# Processor.net
KiCad netlist of a schematic drawn in Altium Designer
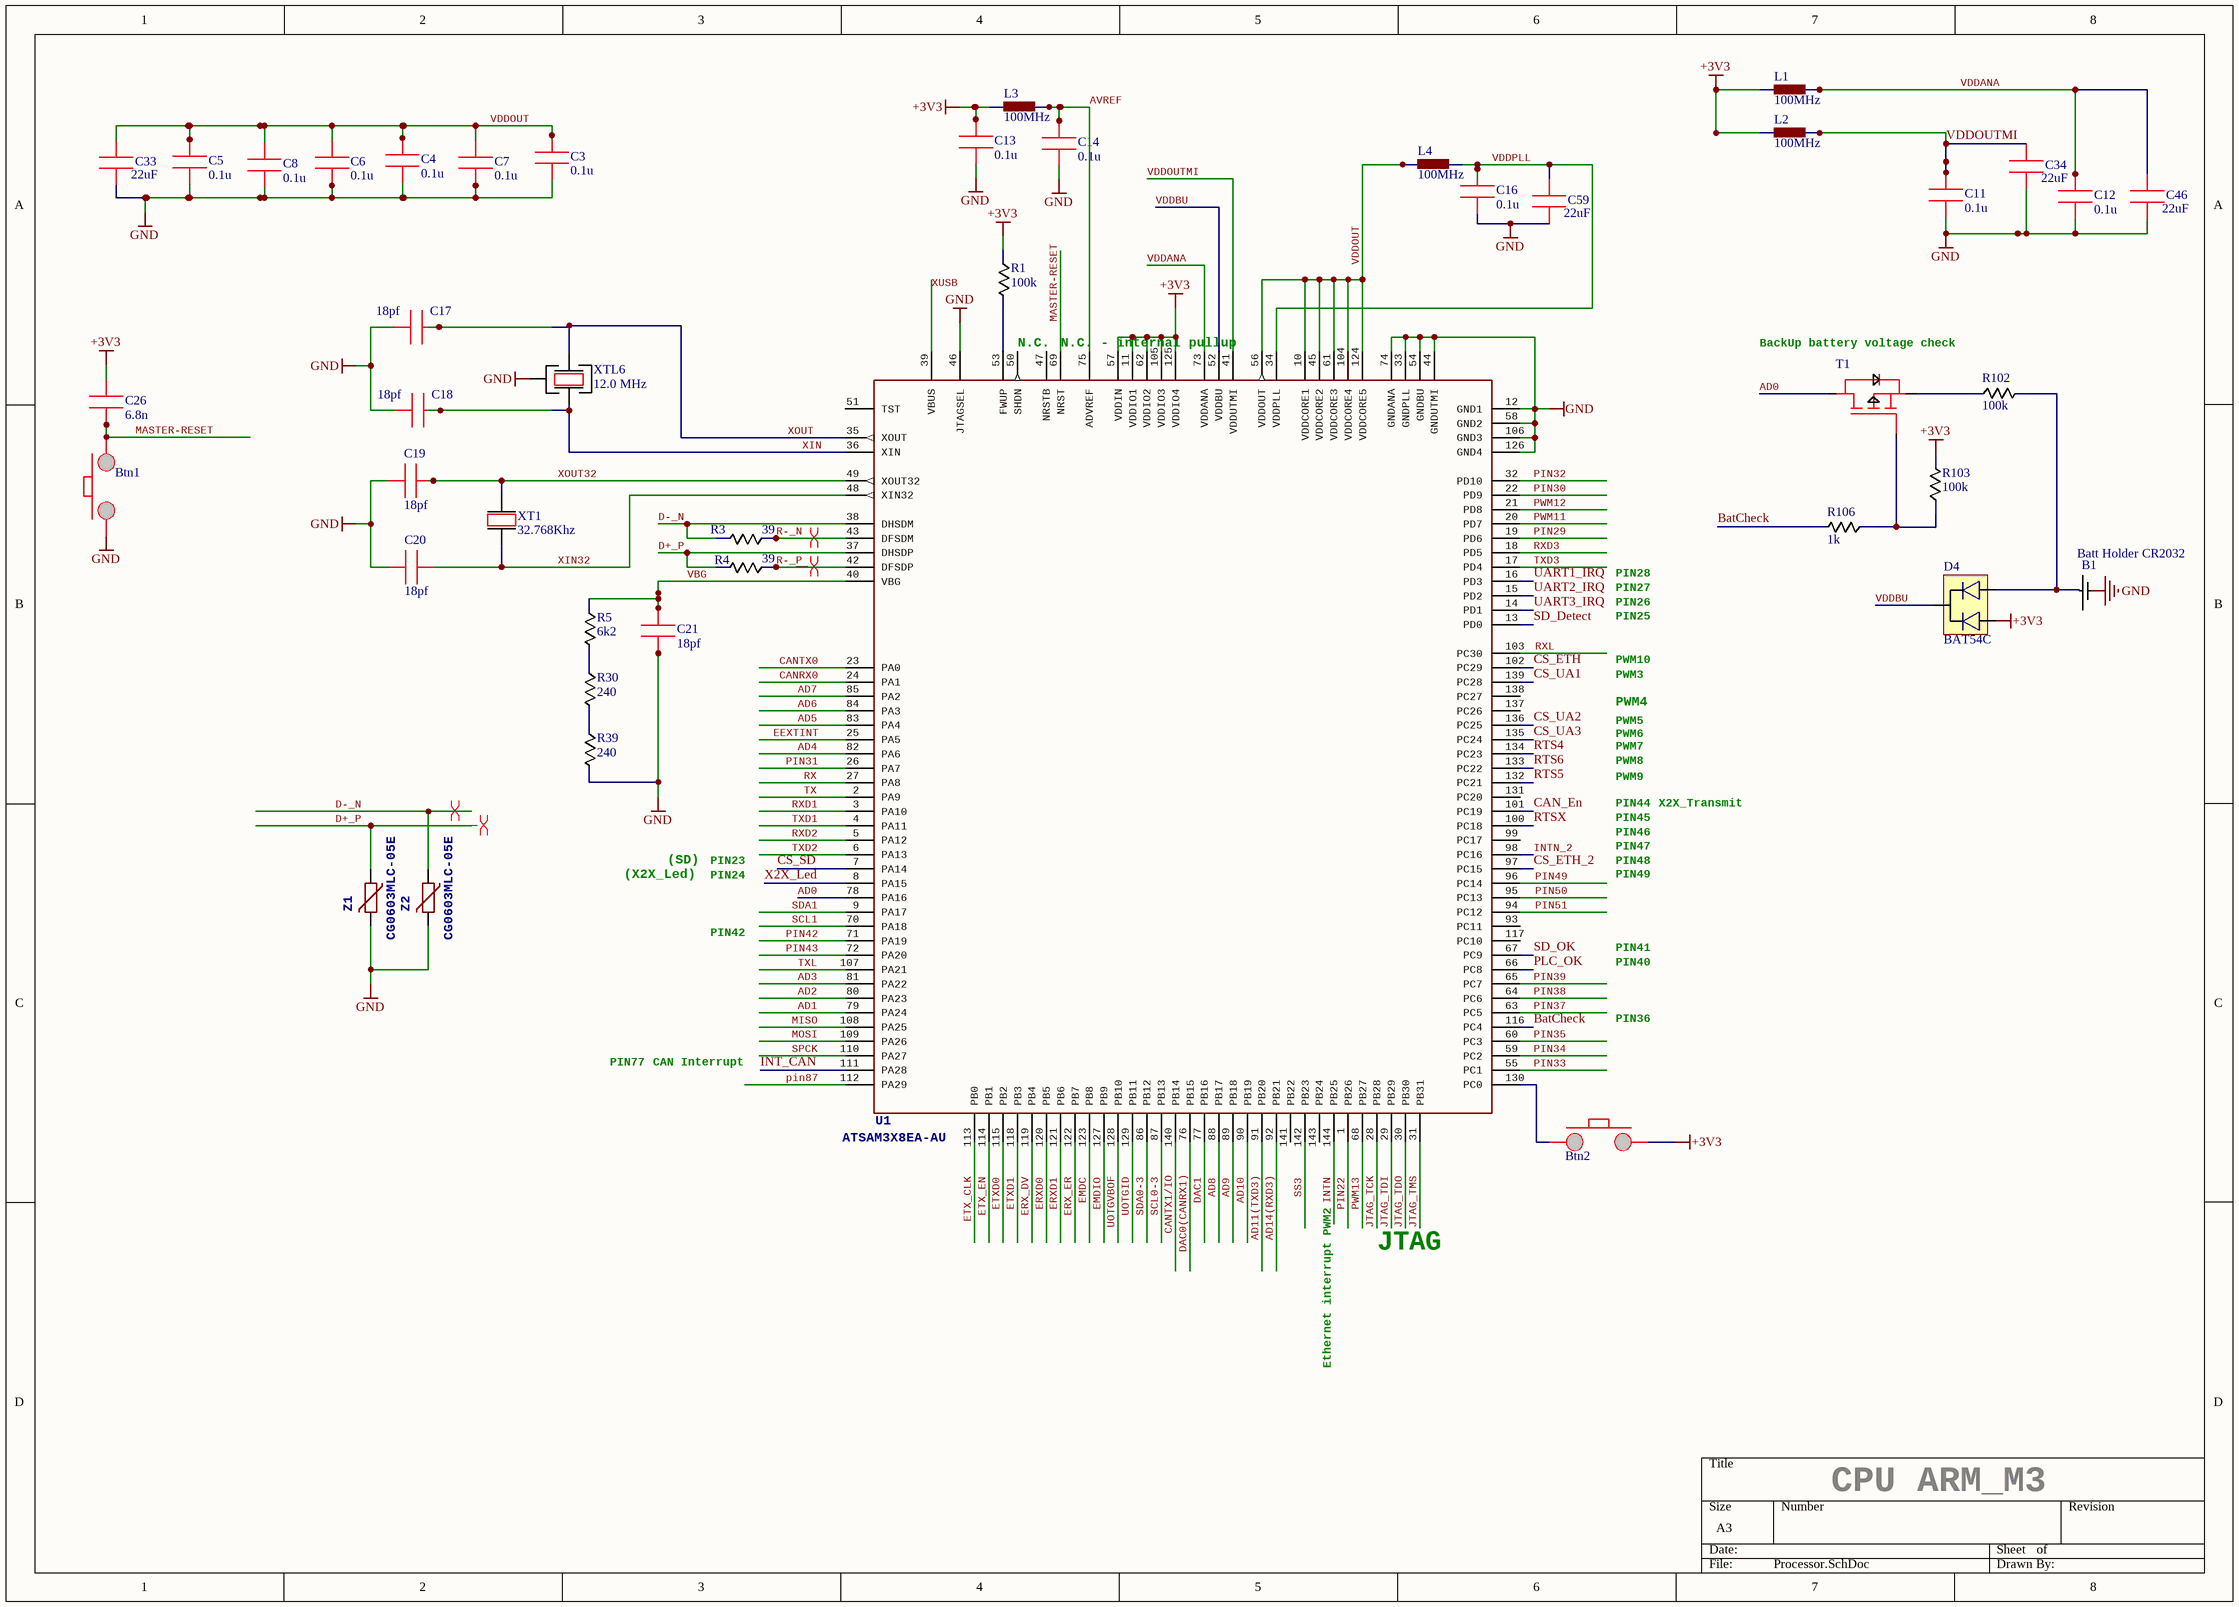
[diagram p0: Processor.SchDoc]

(export (version "E")
  (design (tool "Eeschema 10.0.6"))
  (components
    (comp (ref "B1")
      (value "Batt Holder CR2032")
      (footprint "Batt Holder CR2032")
      (description "1734178-1")
      (libsource (lib "kontr") (part "Batt Holder CR2032"))
    )
    (comp (ref "Btn1")
      (value "Tact Switch")
      (footprint "Tact Switch")
      (description "KLS7-TS6606-4.3-180")
      (libsource (lib "kontr") (part "Tact Switch"))
    )
    (comp (ref "Btn2")
      (value "Tact Switch")
      (footprint "Tact Switch")
      (description "KLS7-TS6606-4.3-180")
      (libsource (lib "kontr") (part "Tact Switch"))
    )
    (comp (ref "C3") (value "0.1u") (footprint "0603 CAP") (libsource (lib "kontr") (part "Capasitor 0805")))
    (comp (ref "C4") (value "0.1u") (footprint "0603 CAP") (libsource (lib "kontr") (part "Capasitor 0805")))
    (comp (ref "C5") (value "0.1u") (footprint "0603 CAP") (libsource (lib "kontr") (part "Capasitor 0805")))
    (comp (ref "C6") (value "0.1u") (footprint "0603 CAP") (libsource (lib "kontr") (part "Capasitor 0805")))
    (comp (ref "C7") (value "0.1u") (footprint "0603 CAP") (libsource (lib "kontr") (part "Capasitor 0805")))
    (comp (ref "C8") (value "0.1u") (footprint "0603 CAP") (libsource (lib "kontr") (part "Capasitor 0805")))
    (comp (ref "C11") (value "0.1u") (footprint "0603 CAP") (libsource (lib "kontr") (part "Capasitor 0805")))
    (comp (ref "C12") (value "0.1u") (footprint "0603 CAP") (libsource (lib "kontr") (part "Capasitor 0805")))
    (comp (ref "C13") (value "0.1u") (footprint "0603 CAP") (libsource (lib "kontr") (part "Capasitor 0805")))
    (comp (ref "C14") (value "0.1u") (footprint "0603 CAP") (libsource (lib "kontr") (part "Capasitor 0805")))
    (comp (ref "C16") (value "0.1u") (footprint "0603 CAP") (libsource (lib "kontr") (part "Capasitor 0805")))
    (comp (ref "C17")
      (value "18pf")
      (footprint "0603 CAP")
      (description "GRM1885C1H180JA01D")
      (libsource (lib "kontr") (part "Capasitor 0805"))
    )
    (comp (ref "C18")
      (value "18pf")
      (footprint "0603 CAP")
      (description "GRM1885C1H180JA01D")
      (libsource (lib "kontr") (part "Capasitor 0805"))
    )
    (comp (ref "C19")
      (value "18pf")
      (footprint "0603 CAP")
      (description "GRM1885C1H180JA01D")
      (libsource (lib "kontr") (part "Capasitor 0805"))
    )
    (comp (ref "C20")
      (value "18pf")
      (footprint "0603 CAP")
      (description "GRM1885C1H180JA01D")
      (libsource (lib "kontr") (part "Capasitor 0805"))
    )
    (comp (ref "C21")
      (value "18pf")
      (footprint "0603 CAP")
      (description "GRM1885C1H180JA01D")
      (libsource (lib "kontr") (part "Capasitor 0805"))
    )
    (comp (ref "C26")
      (value "6.8n")
      (footprint "0603 CAP")
      (description "CC0603KRX7R9BB682")
      (libsource (lib "kontr") (part "0603 CAP"))
    )
    (comp (ref "C33")
      (value "22uF")
      (footprint "CAP CER 1210 NP")
      (description "CC1210KKX5R7BB226")
      (libsource (lib "kontr") (part "0805 Cap"))
    )
    (comp (ref "C34")
      (value "22uF")
      (footprint "CAP CER 1210 NP")
      (description "CC1210KKX5R7BB226")
      (libsource (lib "kontr") (part "0805 Cap"))
    )
    (comp (ref "C46")
      (value "22uF")
      (footprint "CAP CER 1210 NP")
      (description "CC1210KKX5R7BB226")
      (libsource (lib "kontr") (part "0805 Cap"))
    )
    (comp (ref "C59")
      (value "22uF")
      (footprint "CAP CER 1210 NP")
      (description "CC1210KKX5R7BB226")
      (libsource (lib "kontr") (part "0805 Cap"))
    )
    (comp (ref "D4") (value "BAT54C") (footprint "SOT23") (libsource (lib "kontr") (part "BAT54C")))
    (comp (ref "L1")
      (value "100MHz")
      (footprint "0805")
      (description "BLM21PG220SN1D")
      (libsource (lib "kontr") (part "BLM21PG220SN1D"))
    )
    (comp (ref "L2")
      (value "100MHz")
      (footprint "0805")
      (description "BLM21PG220SN1D")
      (libsource (lib "kontr") (part "BLM21PG220SN1D"))
    )
    (comp (ref "L3")
      (value "100MHz")
      (footprint "0805")
      (description "BLM21PG220SN1D")
      (libsource (lib "kontr") (part "BLM21PG220SN1D"))
    )
    (comp (ref "L4")
      (value "100MHz")
      (footprint "0805")
      (description "BLM21PG220SN1D")
      (libsource (lib "kontr") (part "BLM21PG220SN1D"))
    )
    (comp (ref "R1")
      (value "100k")
      (footprint "0603 - RES")
      (description "RC0603FR-07100KL")
      (libsource (lib "kontr") (part "Resistor 0805"))
    )
    (comp (ref "R3")
      (value "39")
      (footprint "0603 - RES")
      (description "0805 SMD Resistor")
      (libsource (lib "kontr") (part "Resistor 0805"))
    )
    (comp (ref "R4")
      (value "39")
      (footprint "0603 - RES")
      (description "0805 SMD Resistor")
      (libsource (lib "kontr") (part "Resistor 0805"))
    )
    (comp (ref "R5")
      (value "6k2")
      (footprint "0603 - RES")
      (description "0805 SMD Resistor")
      (libsource (lib "kontr") (part "Resistor 0805"))
    )
    (comp (ref "R30")
      (value "240")
      (footprint "0603 - RES")
      (description "0805 SMD Resistor")
      (libsource (lib "kontr") (part "Resistor 0805"))
    )
    (comp (ref "R39")
      (value "240")
      (footprint "0603 - RES")
      (description "0805 SMD Resistor")
      (libsource (lib "kontr") (part "Resistor 0805"))
    )
    (comp (ref "R102")
      (value "100k")
      (footprint "0603 - RES")
      (description "RC0603FR-07100KL")
      (libsource (lib "kontr") (part "Resistor 0805"))
    )
    (comp (ref "R103")
      (value "100k")
      (footprint "0603 - RES")
      (description "RC0603FR-07100KL")
      (libsource (lib "kontr") (part "Resistor 0805"))
    )
    (comp (ref "R106")
      (value "1k")
      (footprint "0603 - RES")
      (description "RC0603FR-078K2")
      (libsource (lib "kontr") (part "Resistor 0805"))
    )
    (comp (ref "T1") (value "IRLML6302") (footprint "SOT23") (libsource (lib "kontr") (part "IRLML6302")))
    (comp (ref "U1")
      (value "ATSAM3X8EA-AU")
      (footprint "LQFP144")
      (libsource (lib "SmartPrj") (part "ATSAM3X/AAU"))
    )
    (comp (ref "XT1")
      (value "32.768Khz")
      (footprint "XTAL KX-327T")
      (description "KX – 327XS")
      (libsource (lib "kontr") (part "KX – 327XS"))
    )
    (comp (ref "XTL6")
      (value "12.0 MHz")
      (footprint "XTAL KX-7T")
      (description "Geyer KX-7 12.0 MHz")
      (libsource (lib "PLC M3") (part "KX-7"))
    )
    (comp (ref "Z1")
      (value "CG0603MLC-05E")
      (footprint "0603 - RES")
      (description "<b>VARISTOR</b>")
      (libsource (lib "varistor") (part "VARISTORCN0603"))
    )
    (comp (ref "Z2")
      (value "CG0603MLC-05E")
      (footprint "0603 - RES")
      (description "<b>VARISTOR</b>")
      (libsource (lib "varistor") (part "VARISTORCN0603"))
    )
  )
  (nets
    (net (code "1") (name "+3V3") (class "Default")
      (node (ref "Btn2") (pin "1") (pinfunction "1_1") (pintype "passive"))
      (node (ref "C13") (pin "2") (pinfunction "2_2") (pintype "passive"))
      (node (ref "C26") (pin "2") (pinfunction "2_2") (pintype "passive"))
      (node (ref "D4") (pin "1") (pinfunction "1_1") (pintype "passive"))
      (node (ref "L1") (pin "1") (pintype "passive"))
      (node (ref "L2") (pin "1") (pintype "passive"))
      (node (ref "L3") (pin "1") (pintype "passive"))
      (node (ref "R1") (pin "1") (pintype "passive"))
      (node (ref "R103") (pin "2") (pintype "passive"))
      (node (ref "U1") (pin "105") (pinfunction "VDDIO3_105") (pintype "power_in"))
      (node (ref "U1") (pin "11") (pinfunction "VDDIO1_11") (pintype "power_in"))
      (node (ref "U1") (pin "125") (pinfunction "VDDIO4_125") (pintype "power_in"))
      (node (ref "U1") (pin "57") (pinfunction "VDDIN_57") (pintype "power_in"))
      (node (ref "U1") (pin "62") (pinfunction "VDDIO2_62") (pintype "power_in"))
    )
    (net (code "2") (name "/AD0") (class "Default")
      (node (ref "T1") (pin "3") (pinfunction "3_3") (pintype "passive"))
      (node (ref "U1") (pin "78") (pinfunction "PA16_78") (pintype "passive"))
    )
    (net (code "3") (name "/AD1") (class "Default")
      (node (ref "U1") (pin "79") (pinfunction "PA24_79") (pintype "passive"))
    )
    (net (code "4") (name "/AD2") (class "Default")
      (node (ref "U1") (pin "80") (pinfunction "PA23_80") (pintype "passive"))
    )
    (net (code "5") (name "/AD3") (class "Default")
      (node (ref "U1") (pin "81") (pinfunction "PA22_81") (pintype "passive"))
    )
    (net (code "6") (name "/AD4") (class "Default")
      (node (ref "U1") (pin "82") (pinfunction "PA6_82") (pintype "passive"))
    )
    (net (code "7") (name "/AD5") (class "Default")
      (node (ref "U1") (pin "83") (pinfunction "PA4_83") (pintype "passive"))
    )
    (net (code "8") (name "/AD6") (class "Default")
      (node (ref "U1") (pin "84") (pinfunction "PA3_84") (pintype "passive"))
    )
    (net (code "9") (name "/AD7") (class "Default")
      (node (ref "U1") (pin "85") (pinfunction "PA2_85") (pintype "passive"))
    )
    (net (code "10") (name "/AD8") (class "Default")
      (node (ref "U1") (pin "88") (pinfunction "PB17_88") (pintype "passive"))
    )
    (net (code "11") (name "/AD9") (class "Default")
      (node (ref "U1") (pin "89") (pinfunction "PB18_89") (pintype "passive"))
    )
    (net (code "12") (name "/AD10") (class "Default")
      (node (ref "U1") (pin "90") (pinfunction "PB19_90") (pintype "passive"))
    )
    (net (code "13") (name "/AD11(TXD3)") (class "Default")
      (node (ref "U1") (pin "91") (pinfunction "PB20_91") (pintype "passive"))
    )
    (net (code "14") (name "/AD14(RXD3)") (class "Default")
      (node (ref "U1") (pin "92") (pinfunction "PB21_92") (pintype "passive"))
    )
    (net (code "15") (name "/AVREF") (class "Default")
      (node (ref "C14") (pin "2") (pinfunction "2_2") (pintype "passive"))
      (node (ref "L3") (pin "2") (pintype "passive"))
      (node (ref "U1") (pin "75") (pinfunction "ADVREF_75") (pintype "power_in"))
    )
    (net (code "16") (name "/BatCheck") (class "Default")
      (node (ref "R106") (pin "2") (pintype "passive"))
      (node (ref "U1") (pin "116") (pinfunction "PC4_116") (pintype "passive"))
    )
    (net (code "17") (name "/CANRX0") (class "Default")
      (node (ref "U1") (pin "24") (pinfunction "PA1_24") (pintype "passive"))
    )
    (net (code "18") (name "/CANTX0") (class "Default")
      (node (ref "U1") (pin "23") (pinfunction "PA0_23") (pintype "passive"))
    )
    (net (code "19") (name "/CANTX1{slash}IO") (class "Default")
      (node (ref "U1") (pin "140") (pinfunction "PB14_140") (pintype "passive"))
    )
    (net (code "20") (name "/CAN_En") (class "Default")
      (node (ref "U1") (pin "101") (pinfunction "PC19_101") (pintype "passive"))
    )
    (net (code "21") (name "/CS_ETH") (class "Default")
      (node (ref "U1") (pin "102") (pinfunction "PC29_102") (pintype "passive"))
    )
    (net (code "22") (name "/CS_ETH_2") (class "Default")
      (node (ref "U1") (pin "97") (pinfunction "PC15_97") (pintype "passive"))
    )
    (net (code "23") (name "/CS_SD") (class "Default")
      (node (ref "U1") (pin "7") (pinfunction "PA14_7") (pintype "passive"))
    )
    (net (code "24") (name "/CS_UA1") (class "Default")
      (node (ref "U1") (pin "139") (pinfunction "PC28_139") (pintype "passive"))
    )
    (net (code "25") (name "/CS_UA2") (class "Default")
      (node (ref "U1") (pin "136") (pinfunction "PC25_136") (pintype "passive"))
    )
    (net (code "26") (name "/CS_UA3") (class "Default")
      (node (ref "U1") (pin "135") (pinfunction "PC24_135") (pintype "passive"))
    )
    (net (code "27") (name "/D+_P") (class "Default")
      (node (ref "R4") (pin "2") (pintype "passive"))
      (node (ref "U1") (pin "37") (pinfunction "DHSDP_37") (pintype "passive"))
      (node (ref "Z1") (pin "1") (pinfunction "1_1") (pintype "passive"))
    )
    (net (code "28") (name "/D-_N") (class "Default")
      (node (ref "R3") (pin "2") (pintype "passive"))
      (node (ref "U1") (pin "38") (pinfunction "DHSDM_38") (pintype "passive"))
      (node (ref "Z2") (pin "1") (pinfunction "1_1") (pintype "passive"))
    )
    (net (code "29") (name "/DAC0(CANRX1)") (class "Default")
      (node (ref "U1") (pin "76") (pinfunction "PB15_76") (pintype "passive"))
    )
    (net (code "30") (name "/DAC1") (class "Default")
      (node (ref "U1") (pin "77") (pinfunction "PB16_77") (pintype "passive"))
    )
    (net (code "31") (name "/EEXTINT") (class "Default")
      (node (ref "U1") (pin "25") (pinfunction "PA5_25") (pintype "passive"))
    )
    (net (code "32") (name "/EMDC") (class "Default")
      (node (ref "U1") (pin "123") (pinfunction "PB8_123") (pintype "passive"))
    )
    (net (code "33") (name "/EMDIO") (class "Default")
      (node (ref "U1") (pin "127") (pinfunction "PB9_127") (pintype "passive"))
    )
    (net (code "34") (name "/ERXD0") (class "Default")
      (node (ref "U1") (pin "120") (pinfunction "PB5_120") (pintype "passive"))
    )
    (net (code "35") (name "/ERXD1") (class "Default")
      (node (ref "U1") (pin "121") (pinfunction "PB6_121") (pintype "passive"))
    )
    (net (code "36") (name "/ERX_DV") (class "Default")
      (node (ref "U1") (pin "119") (pinfunction "PB4_119") (pintype "passive"))
    )
    (net (code "37") (name "/ERX_ER") (class "Default")
      (node (ref "U1") (pin "122") (pinfunction "PB7_122") (pintype "passive"))
    )
    (net (code "38") (name "/ETXD0") (class "Default")
      (node (ref "U1") (pin "115") (pinfunction "PB2_115") (pintype "passive"))
    )
    (net (code "39") (name "/ETXD1") (class "Default")
      (node (ref "U1") (pin "118") (pinfunction "PB3_118") (pintype "passive"))
    )
    (net (code "40") (name "/ETX_CLK") (class "Default")
      (node (ref "U1") (pin "113") (pinfunction "PB0_113") (pintype "passive"))
    )
    (net (code "41") (name "/ETX_EN") (class "Default")
      (node (ref "U1") (pin "114") (pinfunction "PB1_114") (pintype "passive"))
    )
    (net (code "42") (name "/INTN") (class "Default")
      (node (ref "U1") (pin "144") (pinfunction "PB25_144") (pintype "passive"))
    )
    (net (code "43") (name "/INTN_2") (class "Default")
      (node (ref "U1") (pin "98") (pinfunction "PC16_98") (pintype "passive"))
    )
    (net (code "44") (name "/INT_CAN") (class "Default")
      (node (ref "U1") (pin "111") (pinfunction "PA28_111") (pintype "passive"))
    )
    (net (code "45") (name "/JTAG_TCK") (class "Default")
      (node (ref "U1") (pin "28") (pinfunction "PB28_28") (pintype "passive"))
    )
    (net (code "46") (name "/JTAG_TDI") (class "Default")
      (node (ref "U1") (pin "29") (pinfunction "PB29_29") (pintype "passive"))
    )
    (net (code "47") (name "/JTAG_TDO") (class "Default")
      (node (ref "U1") (pin "30") (pinfunction "PB30_30") (pintype "passive"))
    )
    (net (code "48") (name "/JTAG_TMS") (class "Default")
      (node (ref "U1") (pin "31") (pinfunction "PB31_31") (pintype "passive"))
    )
    (net (code "49") (name "/MASTER-RESET") (class "Default")
      (node (ref "Btn1") (pin "1") (pinfunction "1_1") (pintype "passive"))
      (node (ref "C26") (pin "1") (pinfunction "1_1") (pintype "passive"))
      (node (ref "U1") (pin "69") (pinfunction "NRST_69") (pintype "passive"))
    )
    (net (code "50") (name "/MISO") (class "Default")
      (node (ref "U1") (pin "108") (pinfunction "PA25_108") (pintype "passive"))
    )
    (net (code "51") (name "/MOSI") (class "Default")
      (node (ref "U1") (pin "109") (pinfunction "PA26_109") (pintype "passive"))
    )
    (net (code "52") (name "/PIN22") (class "Default")
      (node (ref "U1") (pin "1") (pinfunction "PB26_1") (pintype "passive"))
    )
    (net (code "53") (name "/PIN29") (class "Default")
      (node (ref "U1") (pin "19") (pinfunction "PD6_19") (pintype "passive"))
    )
    (net (code "54") (name "/PIN30") (class "Default")
      (node (ref "U1") (pin "22") (pinfunction "PD9_22") (pintype "passive"))
    )
    (net (code "55") (name "/PIN31") (class "Default")
      (node (ref "U1") (pin "26") (pinfunction "PA7_26") (pintype "passive"))
    )
    (net (code "56") (name "/PIN32") (class "Default")
      (node (ref "U1") (pin "32") (pinfunction "PD10_32") (pintype "passive"))
    )
    (net (code "57") (name "/PIN33") (class "Default")
      (node (ref "U1") (pin "55") (pinfunction "PC1_55") (pintype "passive"))
    )
    (net (code "58") (name "/PIN34") (class "Default")
      (node (ref "U1") (pin "59") (pinfunction "PC2_59") (pintype "passive"))
    )
    (net (code "59") (name "/PIN35") (class "Default")
      (node (ref "U1") (pin "60") (pinfunction "PC3_60") (pintype "passive"))
    )
    (net (code "60") (name "/PIN37") (class "Default")
      (node (ref "U1") (pin "63") (pinfunction "PC5_63") (pintype "passive"))
    )
    (net (code "61") (name "/PIN38") (class "Default")
      (node (ref "U1") (pin "64") (pinfunction "PC6_64") (pintype "passive"))
    )
    (net (code "62") (name "/PIN39") (class "Default")
      (node (ref "U1") (pin "65") (pinfunction "PC7_65") (pintype "passive"))
    )
    (net (code "63") (name "/PIN42") (class "Default")
      (node (ref "U1") (pin "71") (pinfunction "PA19_71") (pintype "passive"))
    )
    (net (code "64") (name "/PIN43") (class "Default")
      (node (ref "U1") (pin "72") (pinfunction "PA20_72") (pintype "passive"))
    )
    (net (code "65") (name "/PIN49") (class "Default")
      (node (ref "U1") (pin "96") (pinfunction "PC14_96") (pintype "passive"))
    )
    (net (code "66") (name "/PIN50") (class "Default")
      (node (ref "U1") (pin "95") (pinfunction "PC13_95") (pintype "passive"))
    )
    (net (code "67") (name "/PIN51") (class "Default")
      (node (ref "U1") (pin "94") (pinfunction "PC12_94") (pintype "passive"))
    )
    (net (code "68") (name "/PLC_OK") (class "Default")
      (node (ref "U1") (pin "66") (pinfunction "PC8_66") (pintype "passive"))
    )
    (net (code "69") (name "/PWM11") (class "Default")
      (node (ref "U1") (pin "20") (pinfunction "PD7_20") (pintype "passive"))
    )
    (net (code "70") (name "/PWM12") (class "Default")
      (node (ref "U1") (pin "21") (pinfunction "PD8_21") (pintype "passive"))
    )
    (net (code "71") (name "/PWM13") (class "Default")
      (node (ref "U1") (pin "68") (pinfunction "PB27_68") (pintype "passive"))
    )
    (net (code "72") (name "/R-_N") (class "Default")
      (node (ref "R3") (pin "1") (pintype "passive"))
      (node (ref "U1") (pin "43") (pinfunction "DFSDM_43") (pintype "passive"))
    )
    (net (code "73") (name "/R-_P") (class "Default")
      (node (ref "R4") (pin "1") (pintype "passive"))
      (node (ref "U1") (pin "42") (pinfunction "DFSDP_42") (pintype "passive"))
    )
    (net (code "74") (name "/RTS4") (class "Default")
      (node (ref "U1") (pin "134") (pinfunction "PC23_134") (pintype "passive"))
    )
    (net (code "75") (name "/RTS5") (class "Default")
      (node (ref "U1") (pin "132") (pinfunction "PC21_132") (pintype "passive"))
    )
    (net (code "76") (name "/RTS6") (class "Default")
      (node (ref "U1") (pin "133") (pinfunction "PC22_133") (pintype "passive"))
    )
    (net (code "77") (name "/RTSX") (class "Default")
      (node (ref "U1") (pin "100") (pinfunction "PC18_100") (pintype "passive"))
    )
    (net (code "78") (name "/RX") (class "Default")
      (node (ref "U1") (pin "27") (pinfunction "PA8_27") (pintype "passive"))
    )
    (net (code "79") (name "/RXD1") (class "Default")
      (node (ref "U1") (pin "3") (pinfunction "PA10_3") (pintype "passive"))
    )
    (net (code "80") (name "/RXD2") (class "Default")
      (node (ref "U1") (pin "5") (pinfunction "PA12_5") (pintype "passive"))
    )
    (net (code "81") (name "/RXD3") (class "Default")
      (node (ref "U1") (pin "18") (pinfunction "PD5_18") (pintype "passive"))
    )
    (net (code "82") (name "/RXL") (class "Default")
      (node (ref "U1") (pin "103") (pinfunction "PC30_103") (pintype "passive"))
    )
    (net (code "83") (name "/SCL0-3") (class "Default")
      (node (ref "U1") (pin "87") (pinfunction "PB13_87") (pintype "passive"))
    )
    (net (code "84") (name "/SCL1") (class "Default")
      (node (ref "U1") (pin "70") (pinfunction "PA18_70") (pintype "passive"))
    )
    (net (code "85") (name "/SDA0-3") (class "Default")
      (node (ref "U1") (pin "86") (pinfunction "PB12_86") (pintype "passive"))
    )
    (net (code "86") (name "/SDA1") (class "Default")
      (node (ref "U1") (pin "9") (pinfunction "PA17_9") (pintype "passive"))
    )
    (net (code "87") (name "/SD_Detect") (class "Default")
      (node (ref "U1") (pin "13") (pinfunction "PD0_13") (pintype "passive"))
    )
    (net (code "88") (name "/SD_OK") (class "Default")
      (node (ref "U1") (pin "67") (pinfunction "PC9_67") (pintype "passive"))
    )
    (net (code "89") (name "/SPCK") (class "Default")
      (node (ref "U1") (pin "110") (pinfunction "PA27_110") (pintype "passive"))
    )
    (net (code "90") (name "/SS3") (class "Default")
      (node (ref "U1") (pin "142") (pinfunction "PB23_142") (pintype "passive"))
    )
    (net (code "91") (name "/TX") (class "Default")
      (node (ref "U1") (pin "2") (pinfunction "PA9_2") (pintype "passive"))
    )
    (net (code "92") (name "/TXD1") (class "Default")
      (node (ref "U1") (pin "4") (pinfunction "PA11_4") (pintype "passive"))
    )
    (net (code "93") (name "/TXD2") (class "Default")
      (node (ref "U1") (pin "6") (pinfunction "PA13_6") (pintype "passive"))
    )
    (net (code "94") (name "/TXD3") (class "Default")
      (node (ref "U1") (pin "17") (pinfunction "PD4_17") (pintype "passive"))
    )
    (net (code "95") (name "/TXL") (class "Default")
      (node (ref "U1") (pin "107") (pinfunction "PA21_107") (pintype "passive"))
    )
    (net (code "96") (name "/UART1_IRQ") (class "Default")
      (node (ref "U1") (pin "16") (pinfunction "PD3_16") (pintype "passive"))
    )
    (net (code "97") (name "/UART2_IRQ") (class "Default")
      (node (ref "U1") (pin "15") (pinfunction "PD2_15") (pintype "passive"))
    )
    (net (code "98") (name "/UART3_IRQ") (class "Default")
      (node (ref "U1") (pin "14") (pinfunction "PD1_14") (pintype "passive"))
    )
    (net (code "99") (name "/UOTGID") (class "Default")
      (node (ref "U1") (pin "129") (pinfunction "PB11_129") (pintype "passive"))
    )
    (net (code "100") (name "/UOTGVBOF") (class "Default")
      (node (ref "U1") (pin "128") (pinfunction "PB10_128") (pintype "passive"))
    )
    (net (code "101") (name "/VBG") (class "Default")
      (node (ref "C21") (pin "2") (pinfunction "2_2") (pintype "passive"))
      (node (ref "R5") (pin "1") (pintype "passive"))
      (node (ref "U1") (pin "40") (pinfunction "VBG_40") (pintype "passive"))
    )
    (net (code "102") (name "/VDDANA") (class "Default")
      (node (ref "C12") (pin "2") (pinfunction "2_2") (pintype "passive"))
      (node (ref "C46") (pin "2") (pinfunction "2_2") (pintype "passive"))
      (node (ref "L1") (pin "2") (pintype "passive"))
      (node (ref "U1") (pin "73") (pinfunction "VDDANA_73") (pintype "power_in"))
    )
    (net (code "103") (name "/VDDBU") (class "Default")
      (node (ref "D4") (pin "3") (pinfunction "2_3") (pintype "passive"))
      (node (ref "U1") (pin "52") (pinfunction "VDDBU_52") (pintype "power_in"))
    )
    (net (code "104") (name "/VDDOUT") (class "Default")
      (node (ref "C3") (pin "2") (pinfunction "2_2") (pintype "passive"))
      (node (ref "C33") (pin "2") (pinfunction "2_2") (pintype "passive"))
      (node (ref "C4") (pin "2") (pinfunction "2_2") (pintype "passive"))
      (node (ref "C5") (pin "2") (pinfunction "2_2") (pintype "passive"))
      (node (ref "C6") (pin "2") (pinfunction "2_2") (pintype "passive"))
      (node (ref "C7") (pin "2") (pinfunction "2_2") (pintype "passive"))
      (node (ref "C8") (pin "2") (pinfunction "2_2") (pintype "passive"))
      (node (ref "L4") (pin "1") (pintype "passive"))
      (node (ref "U1") (pin "10") (pinfunction "VDDCORE1_10") (pintype "passive"))
      (node (ref "U1") (pin "104") (pinfunction "VDDCORE4_104") (pintype "passive"))
      (node (ref "U1") (pin "124") (pinfunction "VDDCORE5_124") (pintype "passive"))
      (node (ref "U1") (pin "45") (pinfunction "VDDCORE2_45") (pintype "passive"))
      (node (ref "U1") (pin "56") (pinfunction "VDDOUT_56") (pintype "output"))
      (node (ref "U1") (pin "61") (pinfunction "VDDCORE3_61") (pintype "passive"))
    )
    (net (code "105") (name "/VDDOUTMI") (class "Default")
      (node (ref "C11") (pin "2") (pinfunction "2_2") (pintype "passive"))
      (node (ref "C34") (pin "2") (pinfunction "2_2") (pintype "passive"))
      (node (ref "L2") (pin "2") (pintype "passive"))
      (node (ref "U1") (pin "41") (pinfunction "VDDUTMI_41") (pintype "passive"))
    )
    (net (code "106") (name "/VDDPLL") (class "Default")
      (node (ref "C16") (pin "2") (pinfunction "2_2") (pintype "passive"))
      (node (ref "C59") (pin "2") (pinfunction "2_2") (pintype "passive"))
      (node (ref "L4") (pin "2") (pintype "passive"))
      (node (ref "U1") (pin "34") (pinfunction "VDDPLL_34") (pintype "passive"))
    )
    (net (code "107") (name "/X2X_Led") (class "Default")
      (node (ref "U1") (pin "8") (pinfunction "PA15_8") (pintype "passive"))
    )
    (net (code "108") (name "/XIN") (class "Default")
      (node (ref "C18") (pin "2") (pinfunction "2_2") (pintype "passive"))
      (node (ref "U1") (pin "36") (pinfunction "XIN_36") (pintype "passive"))
      (node (ref "XTL6") (pin "3") (pinfunction "5_3") (pintype "passive"))
    )
    (net (code "109") (name "/XIN32") (class "Default")
      (node (ref "C20") (pin "1") (pinfunction "1_1") (pintype "passive"))
      (node (ref "U1") (pin "48") (pinfunction "XIN32_48") (pintype "output"))
      (node (ref "XT1") (pin "1") (pinfunction "5_1") (pintype "passive"))
    )
    (net (code "110") (name "/XOUT") (class "Default")
      (node (ref "C17") (pin "2") (pinfunction "2_2") (pintype "passive"))
      (node (ref "U1") (pin "35") (pinfunction "XOUT_35") (pintype "output"))
      (node (ref "XTL6") (pin "1") (pinfunction "5_1") (pintype "passive"))
    )
    (net (code "111") (name "/XOUT32") (class "Default")
      (node (ref "C19") (pin "1") (pinfunction "1_1") (pintype "passive"))
      (node (ref "U1") (pin "49") (pinfunction "XOUT32_49") (pintype "output"))
      (node (ref "XT1") (pin "2") (pinfunction "5_2") (pintype "passive"))
    )
    (net (code "112") (name "/XUSB") (class "Default")
      (node (ref "U1") (pin "39") (pinfunction "VBUS_39") (pintype "power_in"))
    )
    (net (code "113") (name "/pin87") (class "Default")
      (node (ref "U1") (pin "112") (pinfunction "PA29_112") (pintype "passive"))
    )
    (net (code "114") (name "GND") (class "Default")
      (node (ref "B1") (pin "0") (pinfunction "5_0") (pintype "passive"))
      (node (ref "Btn1") (pin "0") (pinfunction "0_0") (pintype "passive"))
      (node (ref "C11") (pin "1") (pinfunction "1_1") (pintype "passive"))
      (node (ref "C12") (pin "1") (pinfunction "1_1") (pintype "passive"))
      (node (ref "C13") (pin "1") (pinfunction "1_1") (pintype "passive"))
      (node (ref "C14") (pin "1") (pinfunction "1_1") (pintype "passive"))
      (node (ref "C16") (pin "1") (pinfunction "1_1") (pintype "passive"))
      (node (ref "C17") (pin "1") (pinfunction "1_1") (pintype "passive"))
      (node (ref "C18") (pin "1") (pinfunction "1_1") (pintype "passive"))
      (node (ref "C19") (pin "2") (pinfunction "2_2") (pintype "passive"))
      (node (ref "C20") (pin "2") (pinfunction "2_2") (pintype "passive"))
      (node (ref "C21") (pin "1") (pinfunction "1_1") (pintype "passive"))
      (node (ref "C3") (pin "1") (pinfunction "1_1") (pintype "passive"))
      (node (ref "C33") (pin "1") (pinfunction "1_1") (pintype "passive"))
      (node (ref "C34") (pin "1") (pinfunction "1_1") (pintype "passive"))
      (node (ref "C4") (pin "1") (pinfunction "1_1") (pintype "passive"))
      (node (ref "C46") (pin "1") (pinfunction "1_1") (pintype "passive"))
      (node (ref "C5") (pin "1") (pinfunction "1_1") (pintype "passive"))
      (node (ref "C59") (pin "1") (pinfunction "1_1") (pintype "passive"))
      (node (ref "C6") (pin "1") (pinfunction "1_1") (pintype "passive"))
      (node (ref "C7") (pin "1") (pinfunction "1_1") (pintype "passive"))
      (node (ref "C8") (pin "1") (pinfunction "1_1") (pintype "passive"))
      (node (ref "R39") (pin "2") (pintype "passive"))
      (node (ref "U1") (pin "106") (pinfunction "GND3_106") (pintype "power_in"))
      (node (ref "U1") (pin "12") (pinfunction "GND1_12") (pintype "power_in"))
      (node (ref "U1") (pin "126") (pinfunction "GND4_126") (pintype "power_in"))
      (node (ref "U1") (pin "33") (pinfunction "GNDPLL_33") (pintype "power_in"))
      (node (ref "U1") (pin "44") (pinfunction "GNDUTMI_44") (pintype "power_in"))
      (node (ref "U1") (pin "46") (pinfunction "JTAGSEL_46") (pintype "passive"))
      (node (ref "U1") (pin "54") (pinfunction "GNDBU_54") (pintype "power_in"))
      (node (ref "U1") (pin "58") (pinfunction "GND2_58") (pintype "power_in"))
      (node (ref "U1") (pin "74") (pinfunction "GNDANA_74") (pintype "power_in"))
      (node (ref "XTL6") (pin "2") (pinfunction "2_2") (pintype "passive"))
      (node (ref "Z1") (pin "2") (pinfunction "2_2") (pintype "passive"))
      (node (ref "Z2") (pin "2") (pinfunction "2_2") (pintype "passive"))
    )
    (net (code "115") (name "Net-(B1-6)") (class "Default")
      (node (ref "B1") (pin "1") (pinfunction "6_1") (pintype "passive"))
      (node (ref "D4") (pin "2") (pinfunction "2_2") (pintype "passive"))
      (node (ref "R102") (pin "2") (pintype "passive"))
    )
    (net (code "116") (name "Net-(R30-Pad1)") (class "Default")
      (node (ref "R30") (pin "1") (pintype "passive"))
      (node (ref "R5") (pin "2") (pintype "passive"))
    )
    (net (code "117") (name "Net-(R30-Pad2)") (class "Default")
      (node (ref "R30") (pin "2") (pintype "passive"))
      (node (ref "R39") (pin "1") (pintype "passive"))
    )
    (net (code "118") (name "Net-(R102-Pad1)") (class "Default")
      (node (ref "R102") (pin "1") (pintype "passive"))
      (node (ref "T1") (pin "2") (pinfunction "2_2") (pintype "passive"))
    )
    (net (code "119") (name "Net-(R103-Pad1)") (class "Default")
      (node (ref "R103") (pin "1") (pintype "passive"))
      (node (ref "R106") (pin "1") (pintype "passive"))
      (node (ref "T1") (pin "1") (pinfunction "1_1") (pintype "passive"))
    )
    (net (code "120") (name "Net-(U1-FWUP)") (class "Default")
      (node (ref "R1") (pin "2") (pintype "passive"))
      (node (ref "U1") (pin "53") (pinfunction "FWUP_53") (pintype "passive"))
    )
    (net (code "121") (name "Net-(U1-PC0)") (class "Default")
      (node (ref "Btn2") (pin "0") (pinfunction "0_0") (pintype "passive"))
      (node (ref "U1") (pin "130") (pinfunction "PC0_130") (pintype "passive"))
    )
    (net (code "122") (name "unconnected-(U1-NRSTB-Pad47)") (class "Default")
      (node (ref "U1") (pin "47") (pinfunction "NRSTB_47") (pintype "passive"))
    )
    (net (code "123") (name "unconnected-(U1-PB22-Pad141)") (class "Default")
      (node (ref "U1") (pin "141") (pinfunction "PB22_141") (pintype "passive"))
    )
    (net (code "124") (name "unconnected-(U1-PB24-Pad143)") (class "Default")
      (node (ref "U1") (pin "143") (pinfunction "PB24_143") (pintype "passive"))
    )
    (net (code "125") (name "unconnected-(U1-PC10-Pad117)") (class "Default")
      (node (ref "U1") (pin "117") (pinfunction "PC10_117") (pintype "passive"))
    )
    (net (code "126") (name "unconnected-(U1-PC11-Pad93)") (class "Default")
      (node (ref "U1") (pin "93") (pinfunction "PC11_93") (pintype "passive"))
    )
    (net (code "127") (name "unconnected-(U1-PC17-Pad99)") (class "Default")
      (node (ref "U1") (pin "99") (pinfunction "PC17_99") (pintype "passive"))
    )
    (net (code "128") (name "unconnected-(U1-PC20-Pad131)") (class "Default")
      (node (ref "U1") (pin "131") (pinfunction "PC20_131") (pintype "passive"))
    )
    (net (code "129") (name "unconnected-(U1-PC26-Pad137)") (class "Default")
      (node (ref "U1") (pin "137") (pinfunction "PC26_137") (pintype "passive"))
    )
    (net (code "130") (name "unconnected-(U1-PC27-Pad138)") (class "Default")
      (node (ref "U1") (pin "138") (pinfunction "PC27_138") (pintype "passive"))
    )
    (net (code "131") (name "unconnected-(U1-SHDN-Pad50)") (class "Default")
      (node (ref "U1") (pin "50") (pinfunction "SHDN_50") (pintype "output"))
    )
    (net (code "132") (name "unconnected-(U1-TST-Pad51)") (class "Default")
      (node (ref "U1") (pin "51") (pinfunction "TST_51") (pintype "passive"))
    )
  )
)
